# HX711_2.net
KiCad netlist of a schematic drawn in Altium Designer
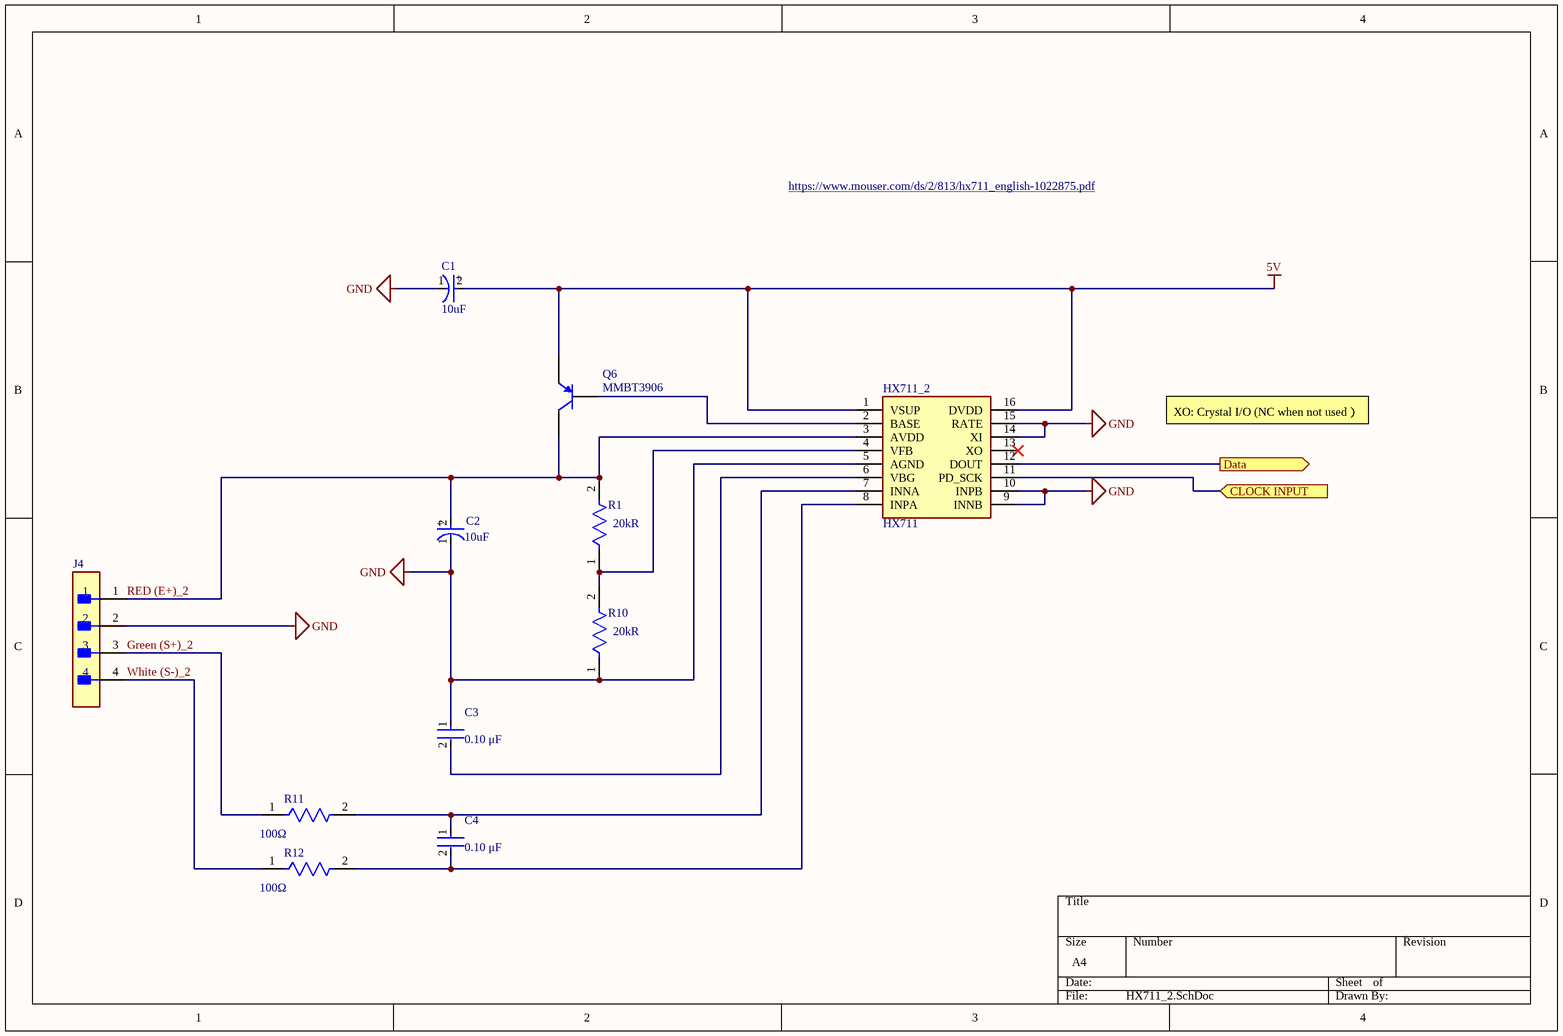
[diagram p0: HX711_2.SchDoc]

(export (version "E")
  (design (tool "Eeschema 10.0.6"))
  (components
    (comp (ref "C1")
      (value "EDK106M035A9BAA")
      (footprint "FP-EDK9B-MFG")
      (description "CAP ALUM 10UF 20% 35V SMD")
      (fields
        (field (name "CAPACITANCE") "10uF")
        (field (name "MANUFACTURER") "Kemet")
        (field (name "OCTOPART") "https://octopart.com/edk106m035a9baa-kemet-26722193")
      )
      (libsource (lib "Altium Content Vault") (part "cf48714ba7e38822c1575c7ec0b6d1f"))
    )
    (comp (ref "C2")
      (value "EDK106M035A9BAA")
      (footprint "FP-EDK9B-MFG")
      (description "CAP ALUM 10UF 20% 35V SMD")
      (fields
        (field (name "CAPACITANCE") "10uF")
        (field (name "MANUFACTURER") "Kemet")
        (field (name "OCTOPART") "https://octopart.com/edk106m035a9baa-kemet-26722193")
      )
      (libsource (lib "Altium Content Vault") (part "cf48714ba7e38822c1575c7ec0b6d1f"))
    )
    (comp (ref "C3")
      (value "0.10 μF")
      (footprint "FP-C0603C-CF-MFG")
      (description "CAP CER 0.1UF 25V X7R 0603")
      (fields
        (field (name "OCTOPART") "https://octopart.com/c0603c104k3rac7411-kemet-9138804")
        (field (name "MANUFACTURER") "KEMET")
      )
      (libsource (lib "Altium Content Vault") (part "b4654b650e69147ec39a6b967a45e02"))
    )
    (comp (ref "C4")
      (value "0.10 μF")
      (footprint "FP-C0603C-CF-MFG")
      (description "CAP CER 0.1UF 25V X7R 0603")
      (fields
        (field (name "OCTOPART") "https://octopart.com/c0603c104k3rac7411-kemet-9138804")
        (field (name "MANUFACTURER") "KEMET")
      )
      (libsource (lib "Altium Content Vault") (part "b4654b650e69147ec39a6b967a45e02"))
    )
    (comp (ref "HX711_2")
      (value "HX711")
      (footprint "SamacSys:SOIC127P600X160-16N")
      (description "Integrated Circuit")
      (libsource (lib "*") (part "HX711"))
    )
    (comp (ref "J4")
      (value "TSW-104-23-T-S")
      (footprint "FP-TSW-104-23-T-S-MFG")
      (description "CONN HEADER VERT 4POS 2.54MM")
      (libsource (lib "Altium Content Vault") (part "f33e0d423099bbb9e64512431cdbdf7"))
    )
    (comp (ref "Q6")
      (value "MMBT3906")
      (footprint "FAIR-SOT23-3_V")
      (description "PNP General-Purpose Amplifier, 40 V, 0.2 A, -55 to 150 degC, 3-Pin SOT23, RoHS, Tape and Reel")
      (fields (field (name "TOLERANCE") "20%"))
      (libsource (lib "Altium Content Vault") (part "BJT-PNP-BEC-3"))
    )
    (comp (ref "R1")
      (value "CRCW060320K0FKEAHP")
      (footprint "FP-CRCW0603-HPe3-MFG")
      (description "RES Thick Film, 20kΩ, 1%, 0.33W, 100ppm/°C, 0603")
      (fields (field (name "RESISTANCE") "20kR") (field (name "TOLERANCE") "1%"))
      (libsource (lib "Altium Content Vault") (part "1029c3af85768c4190bb7ad29bc67b5"))
    )
    (comp (ref "R10")
      (value "CRCW060320K0FKEAHP")
      (footprint "FP-CRCW0603-HPe3-MFG")
      (description "RES Thick Film, 20kΩ, 1%, 0.33W, 100ppm/°C, 0603")
      (fields (field (name "RESISTANCE") "20kR") (field (name "TOLERANCE") "1%"))
      (libsource (lib "Altium Content Vault") (part "1029c3af85768c4190bb7ad29bc67b5"))
    )
    (comp (ref "R11")
      (value "100Ω")
      (footprint "FP-RT0603-MFG")
      (description "RES SMD 100 OHM 1% 1/10W 0603")
      (fields
        (field (name "MANUFACTURER PART NUMBER") "RT0603FRE07100RL")
        (field (name "MANUFACTURER") "Yageo")
      )
      (libsource (lib "Altium Content Vault") (part "1029c3af85768c4190bb7ad29bc67b5"))
    )
    (comp (ref "R12")
      (value "100Ω")
      (footprint "FP-RT0603-MFG")
      (description "RES SMD 100 OHM 1% 1/10W 0603")
      (fields
        (field (name "MANUFACTURER PART NUMBER") "RT0603FRE07100RL")
        (field (name "MANUFACTURER") "Yageo")
      )
      (libsource (lib "Altium Content Vault") (part "1029c3af85768c4190bb7ad29bc67b5"))
    )
  )
  (nets
    (net (code "1") (name "/CLOCK INPUT") (class "Default")
      (node (ref "HX711_2") (pin "11") (pinfunction "PD_SCK_11") (pintype "passive"))
    )
    (net (code "2") (name "/Data") (class "Default")
      (node (ref "HX711_2") (pin "12") (pinfunction "DOUT_12") (pintype "passive"))
    )
    (net (code "3") (name "/Green (S+)_2") (class "Default")
      (node (ref "J4") (pin "3") (pinfunction "3_3") (pintype "passive"))
      (node (ref "R11") (pin "1") (pinfunction "1_1") (pintype "passive"))
    )
    (net (code "4") (name "/RED (E+)_2") (class "Default")
      (node (ref "C2") (pin "2") (pinfunction "A_2") (pintype "passive"))
      (node (ref "HX711_2") (pin "3") (pinfunction "AVDD_3") (pintype "passive"))
      (node (ref "J4") (pin "1") (pinfunction "1_1") (pintype "passive"))
      (node (ref "Q6") (pin "3") (pinfunction "C_3") (pintype "passive"))
      (node (ref "R1") (pin "2") (pinfunction "2_2") (pintype "passive"))
    )
    (net (code "5") (name "/White (S-)_2") (class "Default")
      (node (ref "J4") (pin "4") (pinfunction "4_4") (pintype "passive"))
      (node (ref "R12") (pin "1") (pinfunction "1_1") (pintype "passive"))
    )
    (net (code "6") (name "5V") (class "Default")
      (node (ref "C1") (pin "2") (pinfunction "A_2") (pintype "passive"))
      (node (ref "HX711_2") (pin "1") (pinfunction "VSUP_1") (pintype "passive"))
      (node (ref "HX711_2") (pin "16") (pinfunction "DVDD_16") (pintype "passive"))
      (node (ref "Q6") (pin "2") (pinfunction "E_2") (pintype "passive"))
    )
    (net (code "7") (name "GND") (class "Default")
      (node (ref "C1") (pin "1") (pinfunction "C_1") (pintype "passive"))
      (node (ref "C2") (pin "1") (pinfunction "C_1") (pintype "passive"))
      (node (ref "C3") (pin "1") (pinfunction "1_1") (pintype "passive"))
      (node (ref "HX711_2") (pin "10") (pinfunction "INPB_10") (pintype "passive"))
      (node (ref "HX711_2") (pin "14") (pinfunction "XI_14") (pintype "passive"))
      (node (ref "HX711_2") (pin "15") (pinfunction "RATE_15") (pintype "passive"))
      (node (ref "HX711_2") (pin "5") (pinfunction "AGND_5") (pintype "passive"))
      (node (ref "HX711_2") (pin "9") (pinfunction "INNB_9") (pintype "passive"))
      (node (ref "J4") (pin "2") (pinfunction "2_2") (pintype "passive"))
      (node (ref "R10") (pin "1") (pinfunction "1_1") (pintype "passive"))
    )
    (net (code "8") (name "Net-(HX711_2-BASE)") (class "Default")
      (node (ref "HX711_2") (pin "2") (pinfunction "BASE_2") (pintype "passive"))
      (node (ref "Q6") (pin "1") (pinfunction "B_1") (pintype "passive"))
    )
    (net (code "9") (name "Net-(HX711_2-INNA)") (class "Default")
      (node (ref "C4") (pin "1") (pinfunction "1_1") (pintype "passive"))
      (node (ref "HX711_2") (pin "7") (pinfunction "INNA_7") (pintype "passive"))
      (node (ref "R11") (pin "2") (pinfunction "2_2") (pintype "passive"))
    )
    (net (code "10") (name "Net-(HX711_2-INPA)") (class "Default")
      (node (ref "C4") (pin "2") (pinfunction "2_2") (pintype "passive"))
      (node (ref "HX711_2") (pin "8") (pinfunction "INPA_8") (pintype "passive"))
      (node (ref "R12") (pin "2") (pinfunction "2_2") (pintype "passive"))
    )
    (net (code "11") (name "Net-(HX711_2-VBG)") (class "Default")
      (node (ref "C3") (pin "2") (pinfunction "2_2") (pintype "passive"))
      (node (ref "HX711_2") (pin "6") (pinfunction "VBG_6") (pintype "passive"))
    )
    (net (code "12") (name "Net-(HX711_2-VFB)") (class "Default")
      (node (ref "HX711_2") (pin "4") (pinfunction "VFB_4") (pintype "passive"))
      (node (ref "R1") (pin "1") (pinfunction "1_1") (pintype "passive"))
      (node (ref "R10") (pin "2") (pinfunction "2_2") (pintype "passive"))
    )
    (net (code "13") (name "unconnected-(HX711_2-XO-Pad13)") (class "Default")
      (node (ref "HX711_2") (pin "13") (pinfunction "XO_13") (pintype "passive+no_connect"))
    )
  )
)
